# ScanseSweepv1_1.net
KiCad netlist of a schematic drawn in EAGLE
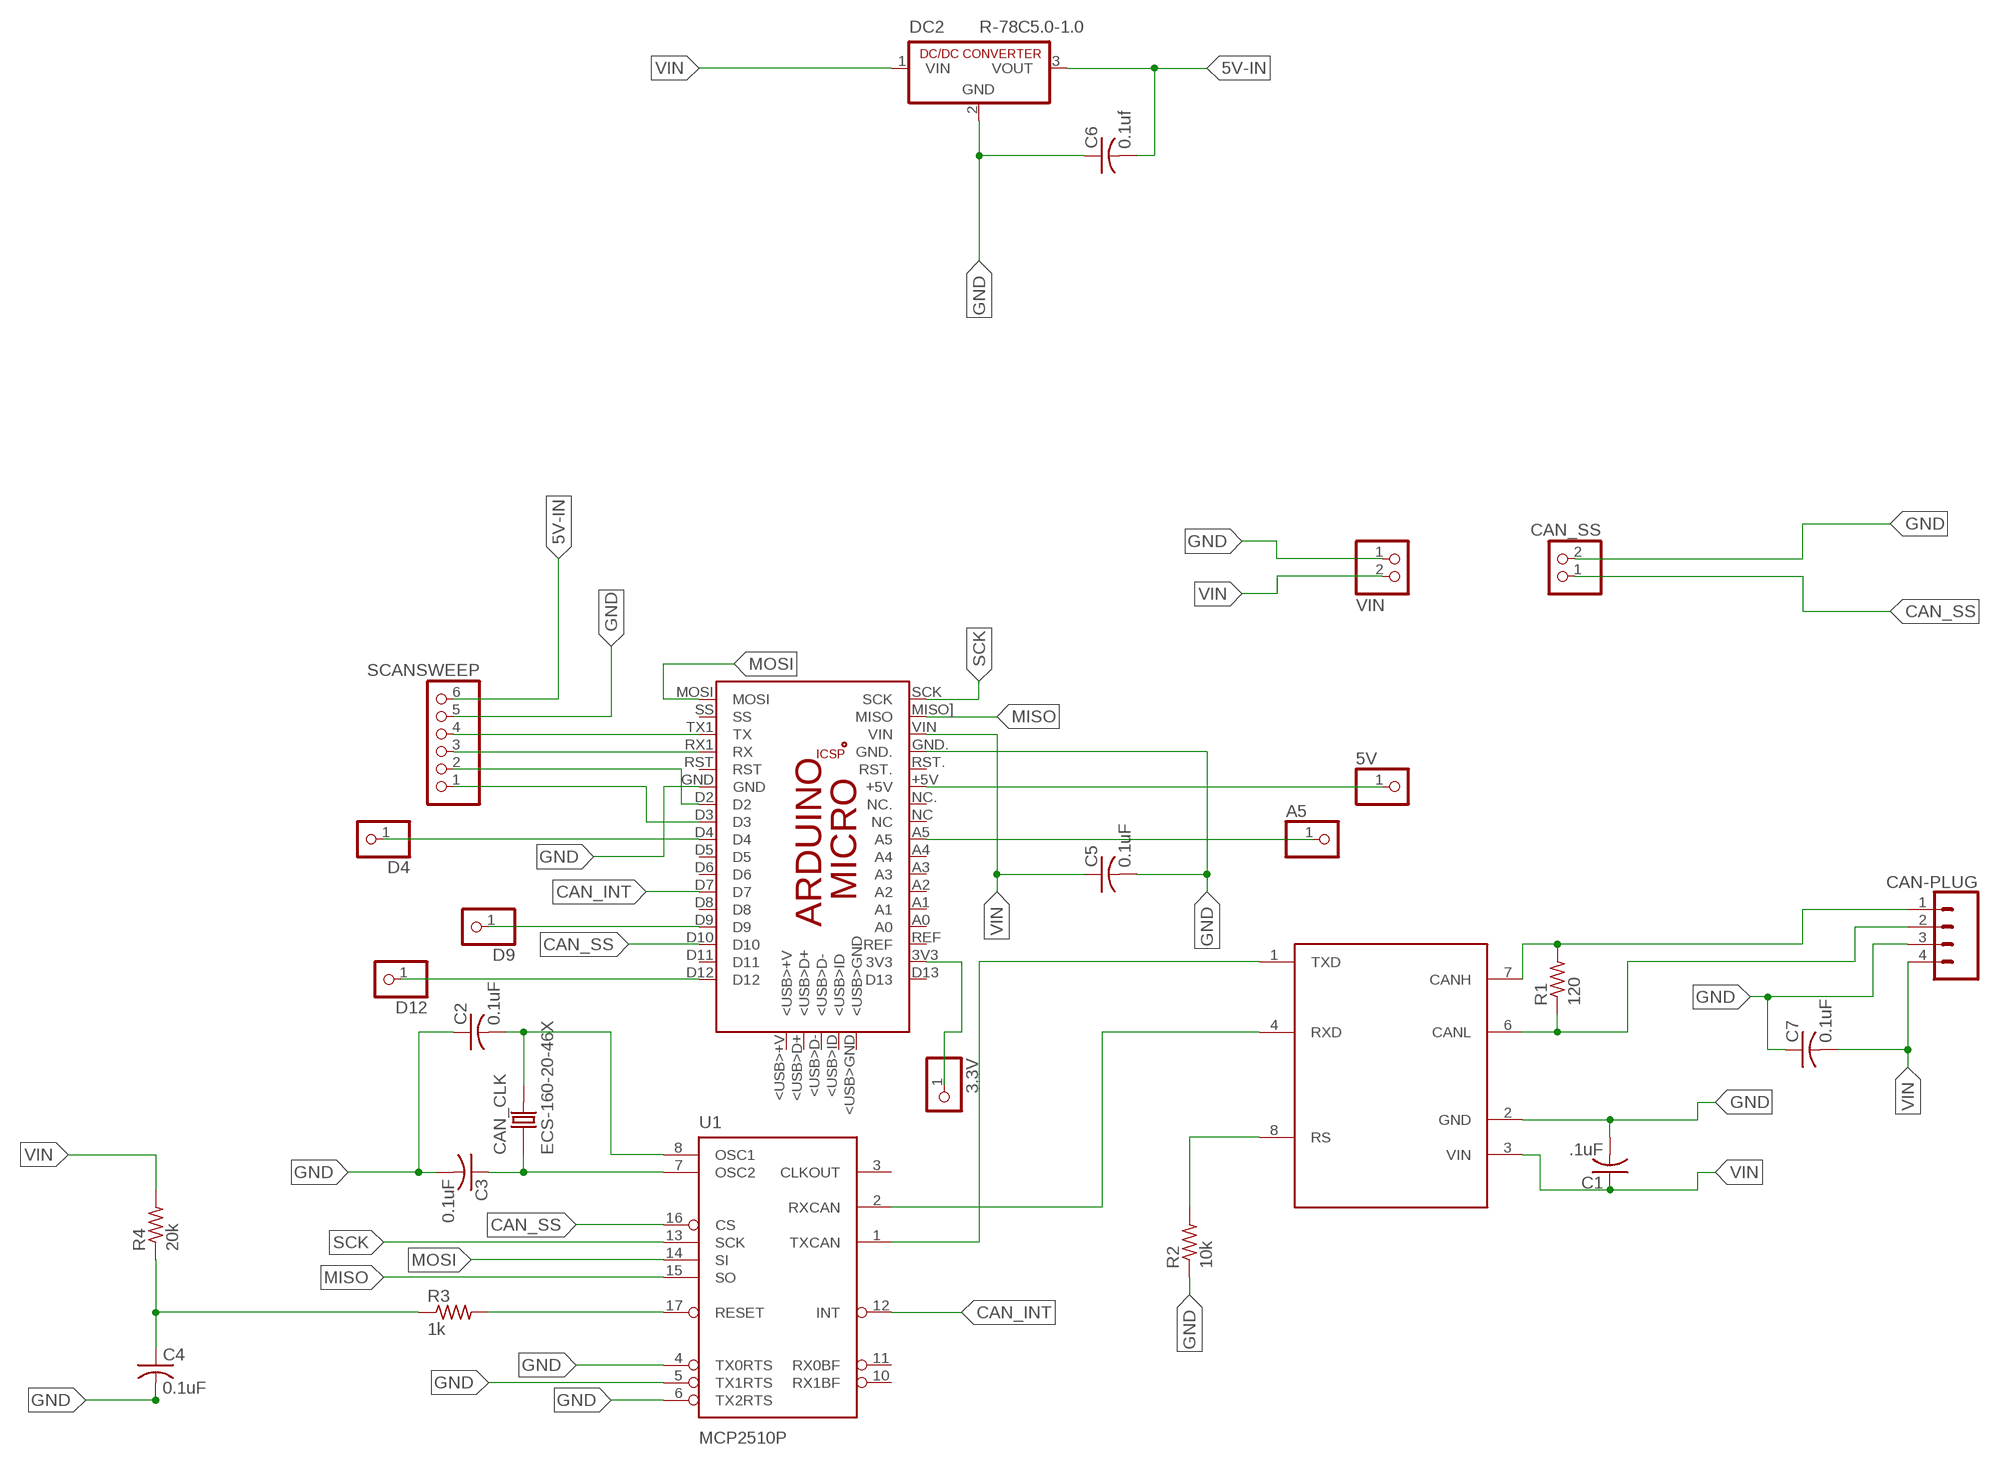
[diagram p0: schematic, sheet 1]

(export (version "E")
  (design (tool "Eeschema 10.0.6"))
  (components
    (comp (ref "3.3V")
      (value "PINHD-1X1")
      (footprint "eagle-import:1X01")
      (libsource (lib "eagle-import") (part "PINHD-1X1"))
    )
    (comp (ref "5V")
      (value "PINHD-1X1")
      (footprint "eagle-import:1X01")
      (libsource (lib "eagle-import") (part "PINHD-1X1"))
    )
    (comp (ref "A5")
      (value "PINHD-1X1")
      (footprint "eagle-import:1X01")
      (libsource (lib "eagle-import") (part "PINHD-1X1"))
    )
    (comp (ref "C1")
      (value ".1uF")
      (footprint "eagle-import:C025-024X044")
      (libsource (lib "eagle-import") (part "C-US025-024X044"))
    )
    (comp (ref "C2")
      (value "0.1uF")
      (footprint "eagle-import:C025-024X044")
      (libsource (lib "eagle-import") (part "C-US025-024X044"))
    )
    (comp (ref "C3")
      (value "0.1uF")
      (footprint "eagle-import:C025-024X044")
      (libsource (lib "eagle-import") (part "C-US025-024X044"))
    )
    (comp (ref "C4")
      (value "0.1uF")
      (footprint "eagle-import:C025-024X044")
      (libsource (lib "eagle-import") (part "C-US025-024X044"))
    )
    (comp (ref "C5")
      (value "0.1uF")
      (footprint "eagle-import:C025-024X044")
      (libsource (lib "eagle-import") (part "C-US025-024X044"))
    )
    (comp (ref "C6")
      (value "0.1uf")
      (footprint "eagle-import:C025-024X044")
      (libsource (lib "eagle-import") (part "C-US025-024X044"))
    )
    (comp (ref "C7")
      (value "0.1uF")
      (footprint "eagle-import:C025-024X044")
      (libsource (lib "eagle-import") (part "C-US025-024X044"))
    )
    (comp (ref "CAN_CLK")
      (value "ECS-160-20-46X")
      (footprint "eagle-import:XTAL_ECS-160-20-46X")
      (fields (field (name "DIGI-KEY_PART_NUMBER") "XC1759-ND") (field (name "MF") "ECS Inc."))
      (libsource (lib "eagle-import") (part "ECS-160-20-46X"))
    )
    (comp (ref "CAN_SS_TEST")
      (value "CAN_SS")
      (footprint "eagle-import:1X02")
      (libsource (lib "eagle-import") (part "PINHD-1X2"))
    )
    (comp (ref "D4")
      (value "PINHD-1X1")
      (footprint "eagle-import:1X01")
      (libsource (lib "eagle-import") (part "PINHD-1X1"))
    )
    (comp (ref "D9")
      (value "PINHD-1X1")
      (footprint "eagle-import:1X01")
      (libsource (lib "eagle-import") (part "PINHD-1X1"))
    )
    (comp (ref "D12")
      (value "PINHD-1X1")
      (footprint "eagle-import:1X01")
      (libsource (lib "eagle-import") (part "PINHD-1X1"))
    )
    (comp (ref "DC2")
      (value "R-78C5.0-1.0")
      (footprint "eagle-import:SIP3")
      (libsource (lib "eagle-import") (part "R-78C-1.05.0"))
    )
    (comp (ref "J1")
      (value "CAN-PLUG")
      (footprint "eagle-import:SCREWTERMINAL-3.5MM-4")
      (libsource (lib "eagle-import") (part "CONN_04SCREW"))
    )
    (comp (ref "PCB1")
      (value "ARDUINO_MICRO")
      (footprint "eagle-import:ARDUINO_MICRO")
      (libsource (lib "eagle-import") (part "ARDUINO_MICRO"))
    )
    (comp (ref "R1")
      (value "120")
      (footprint "eagle-import:0204_5")
      (libsource (lib "eagle-import") (part "R-US_0204/5"))
    )
    (comp (ref "R2")
      (value "10k")
      (footprint "eagle-import:0204_5")
      (libsource (lib "eagle-import") (part "R-US_0204/5"))
    )
    (comp (ref "R3")
      (value "1k")
      (footprint "eagle-import:0204_5")
      (libsource (lib "eagle-import") (part "R-US_0204/5"))
    )
    (comp (ref "R4")
      (value "20k")
      (footprint "eagle-import:0204_5")
      (libsource (lib "eagle-import") (part "R-US_0204/5"))
    )
    (comp (ref "SCANSESWEEP")
      (value "SCANSWEEP")
      (footprint "eagle-import:1X06")
      (libsource (lib "eagle-import") (part "PINHD-1X6"))
    )
    (comp (ref "U$1")
      (value "MCP2551MCP2551")
      (footprint "eagle-import:DIL08")
      (libsource (lib "eagle-import") (part "MCP2551MCP2551"))
    )
    (comp (ref "U1")
      (value "MCP2510P")
      (footprint "eagle-import:DIL18")
      (libsource (lib "eagle-import") (part "MCP2510P"))
    )
    (comp (ref "VIN_TEST")
      (value "VIN")
      (footprint "eagle-import:1X02")
      (libsource (lib "eagle-import") (part "PINHD-1X2"))
    )
  )
  (nets
    (net (code "1") (name "5V-IN") (class "Default")
      (node (ref "C6") (pin "2") (pinfunction "2_2") (pintype "passive"))
      (node (ref "DC2") (pin "3") (pinfunction "VOUT_3") (pintype "passive"))
      (node (ref "SCANSESWEEP") (pin "6") (pinfunction "6_6") (pintype "passive"))
    )
    (net (code "2") (name "CAN_INT") (class "Default")
      (node (ref "PCB1") (pin "D7") (pinfunction "D7_D7") (pintype "bidirectional"))
      (node (ref "U1") (pin "12") (pinfunction "INT_12") (pintype "output"))
    )
    (net (code "3") (name "CAN_SS") (class "Default")
      (node (ref "CAN_SS_TEST") (pin "1") (pinfunction "1_1") (pintype "passive"))
      (node (ref "PCB1") (pin "D10") (pinfunction "D10_D10") (pintype "bidirectional"))
      (node (ref "U1") (pin "16") (pinfunction "CS_16") (pintype "input"))
    )
    (net (code "4") (name "GND") (class "Default")
      (node (ref "C1") (pin "2") (pinfunction "2_2") (pintype "passive"))
      (node (ref "C2") (pin "1") (pinfunction "1_1") (pintype "passive"))
      (node (ref "C3") (pin "2") (pinfunction "2_2") (pintype "passive"))
      (node (ref "C4") (pin "2") (pinfunction "2_2") (pintype "passive"))
      (node (ref "C5") (pin "2") (pinfunction "2_2") (pintype "passive"))
      (node (ref "C6") (pin "1") (pinfunction "1_1") (pintype "passive"))
      (node (ref "C7") (pin "1") (pinfunction "1_1") (pintype "passive"))
      (node (ref "CAN_SS_TEST") (pin "2") (pinfunction "2_2") (pintype "passive"))
      (node (ref "DC2") (pin "2") (pinfunction "GND_2") (pintype "passive"))
      (node (ref "J1") (pin "3") (pinfunction "3_3") (pintype "passive"))
      (node (ref "PCB1") (pin "GND") (pinfunction "GND_GND") (pintype "bidirectional"))
      (node (ref "PCB1") (pin "GND.") (pinfunction "GND._GND.") (pintype "bidirectional"))
      (node (ref "R2") (pin "1") (pinfunction "1_1") (pintype "passive"))
      (node (ref "SCANSESWEEP") (pin "5") (pinfunction "5_5") (pintype "passive"))
      (node (ref "U$1") (pin "2") (pinfunction "GND_2") (pintype "bidirectional"))
      (node (ref "U1") (pin "4") (pinfunction "TX0RTS_4") (pintype "input"))
      (node (ref "U1") (pin "5") (pinfunction "TX1RTS_5") (pintype "input"))
      (node (ref "U1") (pin "6") (pinfunction "TX2RTS_6") (pintype "input"))
      (node (ref "VIN_TEST") (pin "1") (pinfunction "1_1") (pintype "passive"))
    )
    (net (code "5") (name "MISO") (class "Default")
      (node (ref "PCB1") (pin "MISO]") (pinfunction "MISO_MISO]") (pintype "bidirectional"))
      (node (ref "U1") (pin "15") (pinfunction "SO_15") (pintype "output"))
    )
    (net (code "6") (name "MOSI") (class "Default")
      (node (ref "PCB1") (pin "MOSI") (pinfunction "MOSI_MOSI") (pintype "bidirectional"))
      (node (ref "U1") (pin "14") (pinfunction "SI_14") (pintype "input"))
    )
    (net (code "7") (name "Net-(3.3V-Pad1)") (class "Default")
      (node (ref "3.3V") (pin "1") (pinfunction "1_1") (pintype "passive"))
      (node (ref "PCB1") (pin "3V3") (pinfunction "3V3_3V3") (pintype "bidirectional"))
    )
    (net (code "8") (name "Net-(5V-Pad1)") (class "Default")
      (node (ref "5V") (pin "1") (pinfunction "1_1") (pintype "passive"))
      (node (ref "PCB1") (pin "+5V") (pinfunction "+5V_+5V") (pintype "bidirectional"))
    )
    (net (code "9") (name "Net-(A5-Pad1)") (class "Default")
      (node (ref "A5") (pin "1") (pinfunction "1_1") (pintype "passive"))
      (node (ref "PCB1") (pin "A5") (pinfunction "A5_A5") (pintype "bidirectional"))
    )
    (net (code "10") (name "Net-(C4-Pad1)") (class "Default")
      (node (ref "C4") (pin "1") (pinfunction "1_1") (pintype "passive"))
      (node (ref "R3") (pin "1") (pinfunction "1_1") (pintype "passive"))
      (node (ref "R4") (pin "1") (pinfunction "1_1") (pintype "passive"))
    )
    (net (code "11") (name "Net-(D4-Pad1)") (class "Default")
      (node (ref "D4") (pin "1") (pinfunction "1_1") (pintype "passive"))
      (node (ref "PCB1") (pin "D4") (pinfunction "D4_D4") (pintype "bidirectional"))
    )
    (net (code "12") (name "Net-(D9-Pad1)") (class "Default")
      (node (ref "D9") (pin "1") (pinfunction "1_1") (pintype "passive"))
      (node (ref "PCB1") (pin "D9") (pinfunction "D9_D9") (pintype "bidirectional"))
    )
    (net (code "13") (name "Net-(D12-Pad1)") (class "Default")
      (node (ref "D12") (pin "1") (pinfunction "1_1") (pintype "passive"))
      (node (ref "PCB1") (pin "D12") (pinfunction "D12_D12") (pintype "bidirectional"))
    )
    (net (code "14") (name "Net-(PCB1-PadD2)") (class "Default")
      (node (ref "PCB1") (pin "D2") (pinfunction "D2_D2") (pintype "bidirectional"))
      (node (ref "SCANSESWEEP") (pin "2") (pinfunction "2_2") (pintype "passive"))
    )
    (net (code "15") (name "Net-(PCB1-PadD3)") (class "Default")
      (node (ref "PCB1") (pin "D3") (pinfunction "D3_D3") (pintype "bidirectional"))
      (node (ref "SCANSESWEEP") (pin "1") (pinfunction "1_1") (pintype "passive"))
    )
    (net (code "16") (name "Net-(PCB1-RX)") (class "Default")
      (node (ref "PCB1") (pin "RX1") (pinfunction "RX_RX1") (pintype "bidirectional"))
      (node (ref "SCANSESWEEP") (pin "3") (pinfunction "3_3") (pintype "passive"))
    )
    (net (code "17") (name "Net-(PCB1-TX)") (class "Default")
      (node (ref "PCB1") (pin "TX1") (pinfunction "TX_TX1") (pintype "bidirectional"))
      (node (ref "SCANSESWEEP") (pin "4") (pinfunction "4_4") (pintype "passive"))
    )
    (net (code "18") (name "Net-(U$1-CANH)") (class "Default")
      (node (ref "J1") (pin "1") (pinfunction "1_1") (pintype "passive"))
      (node (ref "R1") (pin "2") (pinfunction "2_2") (pintype "passive"))
      (node (ref "U$1") (pin "7") (pinfunction "CANH_7") (pintype "bidirectional"))
    )
    (net (code "19") (name "Net-(U$1-CANL)") (class "Default")
      (node (ref "J1") (pin "2") (pinfunction "2_2") (pintype "passive"))
      (node (ref "R1") (pin "1") (pinfunction "1_1") (pintype "passive"))
      (node (ref "U$1") (pin "6") (pinfunction "CANL_6") (pintype "bidirectional"))
    )
    (net (code "20") (name "Net-(U$1-RS)") (class "Default")
      (node (ref "R2") (pin "2") (pinfunction "2_2") (pintype "passive"))
      (node (ref "U$1") (pin "8") (pinfunction "RS_8") (pintype "bidirectional"))
    )
    (net (code "21") (name "Net-(U$1-RXD)") (class "Default")
      (node (ref "U$1") (pin "4") (pinfunction "RXD_4") (pintype "bidirectional"))
      (node (ref "U1") (pin "2") (pinfunction "RXCAN_2") (pintype "input"))
    )
    (net (code "22") (name "Net-(U$1-TXD)") (class "Default")
      (node (ref "U$1") (pin "1") (pinfunction "TXD_1") (pintype "bidirectional"))
      (node (ref "U1") (pin "1") (pinfunction "TXCAN_1") (pintype "output"))
    )
    (net (code "23") (name "Net-(U1A-OSC1)") (class "Default")
      (node (ref "C2") (pin "2") (pinfunction "2_2") (pintype "passive"))
      (node (ref "CAN_CLK") (pin "2") (pinfunction "2_2") (pintype "passive"))
      (node (ref "U1") (pin "8") (pinfunction "OSC1_8") (pintype "input"))
    )
    (net (code "24") (name "Net-(U1A-OSC2)") (class "Default")
      (node (ref "C3") (pin "1") (pinfunction "1_1") (pintype "passive"))
      (node (ref "CAN_CLK") (pin "1") (pinfunction "1_1") (pintype "passive"))
      (node (ref "U1") (pin "7") (pinfunction "OSC2_7") (pintype "output"))
    )
    (net (code "25") (name "Net-(U1A-RESET)") (class "Default")
      (node (ref "R3") (pin "2") (pinfunction "2_2") (pintype "passive"))
      (node (ref "U1") (pin "17") (pinfunction "RESET_17") (pintype "input"))
    )
    (net (code "26") (name "SCK") (class "Default")
      (node (ref "PCB1") (pin "SCK") (pinfunction "SCK_SCK") (pintype "bidirectional"))
      (node (ref "U1") (pin "13") (pinfunction "SCK_13") (pintype "input"))
    )
    (net (code "27") (name "VIN") (class "Default")
      (node (ref "C1") (pin "1") (pinfunction "1_1") (pintype "passive"))
      (node (ref "C5") (pin "1") (pinfunction "1_1") (pintype "passive"))
      (node (ref "C7") (pin "2") (pinfunction "2_2") (pintype "passive"))
      (node (ref "DC2") (pin "1") (pinfunction "VIN_1") (pintype "passive"))
      (node (ref "J1") (pin "4") (pinfunction "4_4") (pintype "passive"))
      (node (ref "PCB1") (pin "VIN") (pinfunction "VIN_VIN") (pintype "bidirectional"))
      (node (ref "R4") (pin "2") (pinfunction "2_2") (pintype "passive"))
      (node (ref "U$1") (pin "3") (pinfunction "VIN_3") (pintype "bidirectional"))
      (node (ref "VIN_TEST") (pin "2") (pinfunction "2_2") (pintype "passive"))
    )
    (net (code "28") (name "unconnected-(PCB1-Pad5V)") (class "Default")
      (node (ref "PCB1") (pin "5V") (pinfunction "5V_5V") (pintype "bidirectional"))
    )
    (net (code "29") (name "unconnected-(PCB1-Pad<USB>+V)") (class "Default")
      (node (ref "PCB1") (pin "<USB>+V") (pinfunction "<USB>+V_<USB>+V") (pintype "bidirectional"))
    )
    (net (code "30") (name "unconnected-(PCB1-Pad<USB>D+)") (class "Default")
      (node (ref "PCB1") (pin "<USB>D+") (pinfunction "<USB>D+_<USB>D+") (pintype "bidirectional"))
    )
    (net (code "31") (name "unconnected-(PCB1-Pad<USB>D-)") (class "Default")
      (node (ref "PCB1") (pin "<USB>D-") (pinfunction "<USB>D-_<USB>D-") (pintype "bidirectional"))
    )
    (net (code "32") (name "unconnected-(PCB1-Pad<USB>GND)") (class "Default")
      (node (ref "PCB1") (pin "<USB>GND") (pinfunction "<USB>GND_<USB>GND") (pintype "bidirectional"))
    )
    (net (code "33") (name "unconnected-(PCB1-Pad<USB>ID)") (class "Default")
      (node (ref "PCB1") (pin "<USB>ID") (pinfunction "<USB>ID_<USB>ID") (pintype "bidirectional"))
    )
    (net (code "34") (name "unconnected-(PCB1-PadA0)") (class "Default")
      (node (ref "PCB1") (pin "A0") (pinfunction "A0_A0") (pintype "bidirectional"))
    )
    (net (code "35") (name "unconnected-(PCB1-PadA1)") (class "Default")
      (node (ref "PCB1") (pin "A1") (pinfunction "A1_A1") (pintype "bidirectional"))
    )
    (net (code "36") (name "unconnected-(PCB1-PadA2)") (class "Default")
      (node (ref "PCB1") (pin "A2") (pinfunction "A2_A2") (pintype "bidirectional"))
    )
    (net (code "37") (name "unconnected-(PCB1-PadA3)") (class "Default")
      (node (ref "PCB1") (pin "A3") (pinfunction "A3_A3") (pintype "bidirectional"))
    )
    (net (code "38") (name "unconnected-(PCB1-PadA4)") (class "Default")
      (node (ref "PCB1") (pin "A4") (pinfunction "A4_A4") (pintype "bidirectional"))
    )
    (net (code "39") (name "unconnected-(PCB1-PadD5)") (class "Default")
      (node (ref "PCB1") (pin "D5") (pinfunction "D5_D5") (pintype "bidirectional"))
    )
    (net (code "40") (name "unconnected-(PCB1-PadD6)") (class "Default")
      (node (ref "PCB1") (pin "D6") (pinfunction "D6_D6") (pintype "bidirectional"))
    )
    (net (code "41") (name "unconnected-(PCB1-PadD8)") (class "Default")
      (node (ref "PCB1") (pin "D8") (pinfunction "D8_D8") (pintype "bidirectional"))
    )
    (net (code "42") (name "unconnected-(PCB1-PadD11)") (class "Default")
      (node (ref "PCB1") (pin "D11") (pinfunction "D11_D11") (pintype "bidirectional"))
    )
    (net (code "43") (name "unconnected-(PCB1-PadD13)") (class "Default")
      (node (ref "PCB1") (pin "D13") (pinfunction "D13_D13") (pintype "bidirectional"))
    )
    (net (code "44") (name "unconnected-(PCB1-PadGND_)") (class "Default")
      (node (ref "PCB1") (pin "GND_") (pinfunction "GND__GND_") (pintype "bidirectional"))
    )
    (net (code "45") (name "unconnected-(PCB1-PadMISO.)") (class "Default")
      (node (ref "PCB1") (pin "MISO.") (pinfunction "MISO._MISO.") (pintype "bidirectional"))
    )
    (net (code "46") (name "unconnected-(PCB1-PadMOSI.)") (class "Default")
      (node (ref "PCB1") (pin "MOSI.") (pinfunction "MOSI._MOSI.") (pintype "bidirectional"))
    )
    (net (code "47") (name "unconnected-(PCB1-PadNC)") (class "Default")
      (node (ref "PCB1") (pin "NC") (pinfunction "NC_NC") (pintype "bidirectional"))
    )
    (net (code "48") (name "unconnected-(PCB1-PadNC.)") (class "Default")
      (node (ref "PCB1") (pin "NC.") (pinfunction "NC._NC.") (pintype "bidirectional"))
    )
    (net (code "49") (name "unconnected-(PCB1-PadREF)") (class "Default")
      (node (ref "PCB1") (pin "REF") (pinfunction "REF_REF") (pintype "bidirectional"))
    )
    (net (code "50") (name "unconnected-(PCB1-PadRESET..)") (class "Default")
      (node (ref "PCB1") (pin "RESET..") (pinfunction "RESET.._RESET..") (pintype "bidirectional"))
    )
    (net (code "51") (name "unconnected-(PCB1-PadRST)") (class "Default")
      (node (ref "PCB1") (pin "RST") (pinfunction "RST_RST") (pintype "bidirectional"))
    )
    (net (code "52") (name "unconnected-(PCB1-PadRST.)") (class "Default")
      (node (ref "PCB1") (pin "RST.") (pinfunction "RST._RST.") (pintype "bidirectional"))
    )
    (net (code "53") (name "unconnected-(PCB1-PadSCK.)") (class "Default")
      (node (ref "PCB1") (pin "SCK.") (pinfunction "SCK._SCK.") (pintype "bidirectional"))
    )
    (net (code "54") (name "unconnected-(PCB1-PadSS)") (class "Default")
      (node (ref "PCB1") (pin "SS") (pinfunction "SS_SS") (pintype "bidirectional"))
    )
    (net (code "55") (name "unconnected-(U1A-CLKOUT-Pad3)") (class "Default")
      (node (ref "U1") (pin "3") (pinfunction "CLKOUT_3") (pintype "output"))
    )
    (net (code "56") (name "unconnected-(U1A-RX0BF-Pad11)") (class "Default")
      (node (ref "U1") (pin "11") (pinfunction "RX0BF_11") (pintype "output"))
    )
    (net (code "57") (name "unconnected-(U1A-RX1BF-Pad10)") (class "Default")
      (node (ref "U1") (pin "10") (pinfunction "RX1BF_10") (pintype "output"))
    )
  )
)
